# bisstransceiver.net
KiCad netlist of a schematic drawn in EAGLE
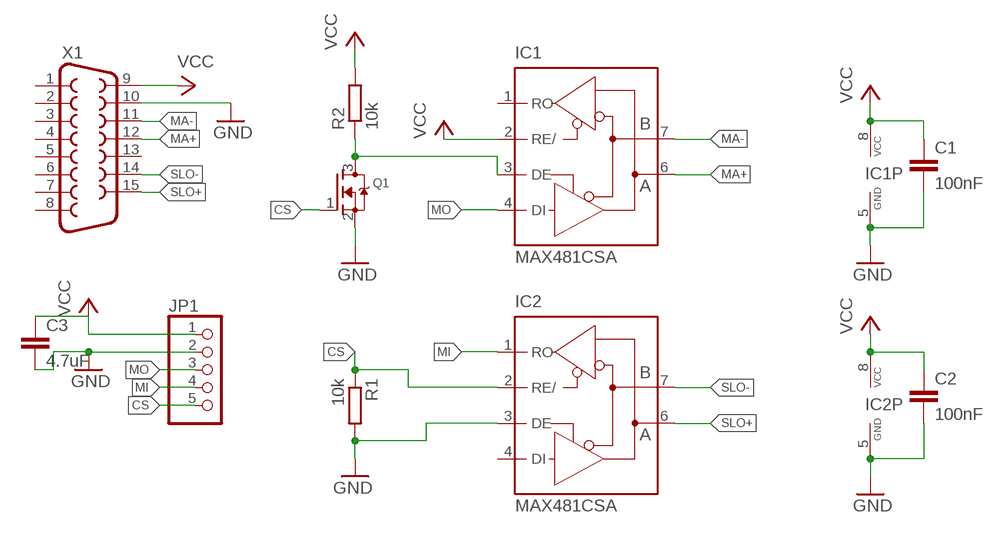
[diagram p0: schematic, sheet 1]

(export (version "E")
  (design (tool "Eeschema 10.0.6"))
  (components
    (comp (ref "C1")
      (value "100nF")
      (footprint "eagle-import:C0603")
      (libsource (lib "eagle-import") (part "C-EUC0603"))
    )
    (comp (ref "C2")
      (value "100nF")
      (footprint "eagle-import:C0603")
      (libsource (lib "eagle-import") (part "C-EUC0603"))
    )
    (comp (ref "C3")
      (value "4.7uF")
      (footprint "eagle-import:C0603")
      (libsource (lib "eagle-import") (part "C-EUC0603"))
    )
    (comp (ref "IC1")
      (value "MAX481CSA")
      (footprint "eagle-import:SO08")
      (fields (field (name "MF") "MAXIM"))
      (libsource (lib "eagle-import") (part "MAX481CSA"))
    )
    (comp (ref "IC2")
      (value "MAX481CSA")
      (footprint "eagle-import:SO08")
      (fields (field (name "MF") "MAXIM"))
      (libsource (lib "eagle-import") (part "MAX481CSA"))
    )
    (comp (ref "JP1")
      (value "PINHD-1X5/90")
      (footprint "eagle-import:1X05_90")
      (libsource (lib "eagle-import") (part "PINHD-1X5/90"))
    )
    (comp (ref "Q1")
      (value "MOSFET-NREFLOW")
      (footprint "eagle-import:SOT23")
      (libsource (lib "eagle-import") (part "MOSFET-NREFLOW"))
    )
    (comp (ref "R1")
      (value "10k")
      (footprint "eagle-import:R0603")
      (libsource (lib "eagle-import") (part "R-EU_R0603"))
    )
    (comp (ref "R2")
      (value "10k")
      (footprint "eagle-import:R0603")
      (libsource (lib "eagle-import") (part "R-EU_R0603"))
    )
    (comp (ref "X1")
      (value "F15HP")
      (footprint "eagle-import:F15HP")
      (libsource (lib "eagle-import") (part "F15HP"))
    )
  )
  (nets
    (net (code "1") (name "CS") (class "Default")
      (node (ref "IC2") (pin "2") (pinfunction "RE/_2") (pintype "input"))
      (node (ref "JP1") (pin "5") (pinfunction "5_5") (pintype "passive"))
      (node (ref "Q1") (pin "1") (pinfunction "G_1") (pintype "bidirectional"))
      (node (ref "R1") (pin "1") (pinfunction "1_1") (pintype "passive"))
    )
    (net (code "2") (name "GND") (class "Default")
      (node (ref "C1") (pin "2") (pinfunction "2_2") (pintype "passive"))
      (node (ref "C2") (pin "2") (pinfunction "2_2") (pintype "passive"))
      (node (ref "C3") (pin "2") (pinfunction "2_2") (pintype "passive"))
      (node (ref "IC1") (pin "5") (pinfunction "GND_5") (pintype "power_in"))
      (node (ref "IC2") (pin "3") (pinfunction "DE_3") (pintype "input"))
      (node (ref "IC2") (pin "5") (pinfunction "GND_5") (pintype "power_in"))
      (node (ref "JP1") (pin "2") (pinfunction "2_2") (pintype "passive"))
      (node (ref "Q1") (pin "2") (pinfunction "S_2") (pintype "bidirectional"))
      (node (ref "R1") (pin "2") (pinfunction "2_2") (pintype "passive"))
      (node (ref "X1") (pin "10") (pinfunction "10_10") (pintype "passive"))
    )
    (net (code "3") (name "MA+") (class "Default")
      (node (ref "IC1") (pin "6") (pinfunction "A_6") (pintype "passive"))
      (node (ref "X1") (pin "12") (pinfunction "12_12") (pintype "passive"))
    )
    (net (code "4") (name "MA-") (class "Default")
      (node (ref "IC1") (pin "7") (pinfunction "B_7") (pintype "passive"))
      (node (ref "X1") (pin "11") (pinfunction "11_11") (pintype "passive"))
    )
    (net (code "5") (name "MI") (class "Default")
      (node (ref "IC2") (pin "1") (pinfunction "RO_1") (pintype "output"))
      (node (ref "JP1") (pin "4") (pinfunction "4_4") (pintype "passive"))
    )
    (net (code "6") (name "MO") (class "Default")
      (node (ref "IC1") (pin "4") (pinfunction "DI_4") (pintype "input"))
      (node (ref "JP1") (pin "3") (pinfunction "3_3") (pintype "passive"))
    )
    (net (code "7") (name "Net-(IC1A-DE)") (class "Default")
      (node (ref "IC1") (pin "3") (pinfunction "DE_3") (pintype "input"))
      (node (ref "Q1") (pin "3") (pinfunction "D_3") (pintype "bidirectional"))
      (node (ref "R2") (pin "1") (pinfunction "1_1") (pintype "passive"))
    )
    (net (code "8") (name "SLO+") (class "Default")
      (node (ref "IC2") (pin "6") (pinfunction "A_6") (pintype "passive"))
      (node (ref "X1") (pin "15") (pinfunction "15_15") (pintype "passive"))
    )
    (net (code "9") (name "SLO-") (class "Default")
      (node (ref "IC2") (pin "7") (pinfunction "B_7") (pintype "passive"))
      (node (ref "X1") (pin "14") (pinfunction "14_14") (pintype "passive"))
    )
    (net (code "10") (name "VCC") (class "Default")
      (node (ref "C1") (pin "1") (pinfunction "1_1") (pintype "passive"))
      (node (ref "C2") (pin "1") (pinfunction "1_1") (pintype "passive"))
      (node (ref "C3") (pin "1") (pinfunction "1_1") (pintype "passive"))
      (node (ref "IC1") (pin "2") (pinfunction "RE/_2") (pintype "input"))
      (node (ref "IC1") (pin "8") (pinfunction "VCC_8") (pintype "power_in"))
      (node (ref "IC2") (pin "8") (pinfunction "VCC_8") (pintype "power_in"))
      (node (ref "JP1") (pin "1") (pinfunction "1_1") (pintype "passive"))
      (node (ref "R2") (pin "2") (pinfunction "2_2") (pintype "passive"))
      (node (ref "X1") (pin "9") (pinfunction "9_9") (pintype "passive"))
    )
    (net (code "11") (name "unconnected-(IC1A-RO-Pad1)") (class "Default")
      (node (ref "IC1") (pin "1") (pinfunction "RO_1") (pintype "output"))
    )
    (net (code "12") (name "unconnected-(IC2A-DI-Pad4)") (class "Default")
      (node (ref "IC2") (pin "4") (pinfunction "DI_4") (pintype "input"))
    )
    (net (code "13") (name "unconnected-(X1-Pad1)") (class "Default")
      (node (ref "X1") (pin "1") (pinfunction "1_1") (pintype "passive"))
    )
    (net (code "14") (name "unconnected-(X1-Pad2)") (class "Default")
      (node (ref "X1") (pin "2") (pinfunction "2_2") (pintype "passive"))
    )
    (net (code "15") (name "unconnected-(X1-Pad3)") (class "Default")
      (node (ref "X1") (pin "3") (pinfunction "3_3") (pintype "passive"))
    )
    (net (code "16") (name "unconnected-(X1-Pad4)") (class "Default")
      (node (ref "X1") (pin "4") (pinfunction "4_4") (pintype "passive"))
    )
    (net (code "17") (name "unconnected-(X1-Pad5)") (class "Default")
      (node (ref "X1") (pin "5") (pinfunction "5_5") (pintype "passive"))
    )
    (net (code "18") (name "unconnected-(X1-Pad6)") (class "Default")
      (node (ref "X1") (pin "6") (pinfunction "6_6") (pintype "passive"))
    )
    (net (code "19") (name "unconnected-(X1-Pad7)") (class "Default")
      (node (ref "X1") (pin "7") (pinfunction "7_7") (pintype "passive"))
    )
    (net (code "20") (name "unconnected-(X1-Pad8)") (class "Default")
      (node (ref "X1") (pin "8") (pinfunction "8_8") (pintype "passive"))
    )
    (net (code "21") (name "unconnected-(X1-Pad13)") (class "Default")
      (node (ref "X1") (pin "13") (pinfunction "13_13") (pintype "passive"))
    )
  )
)
